# ATTINY85_Updated_Design_Extended_Board.net
KiCad netlist of a schematic drawn in EAGLE
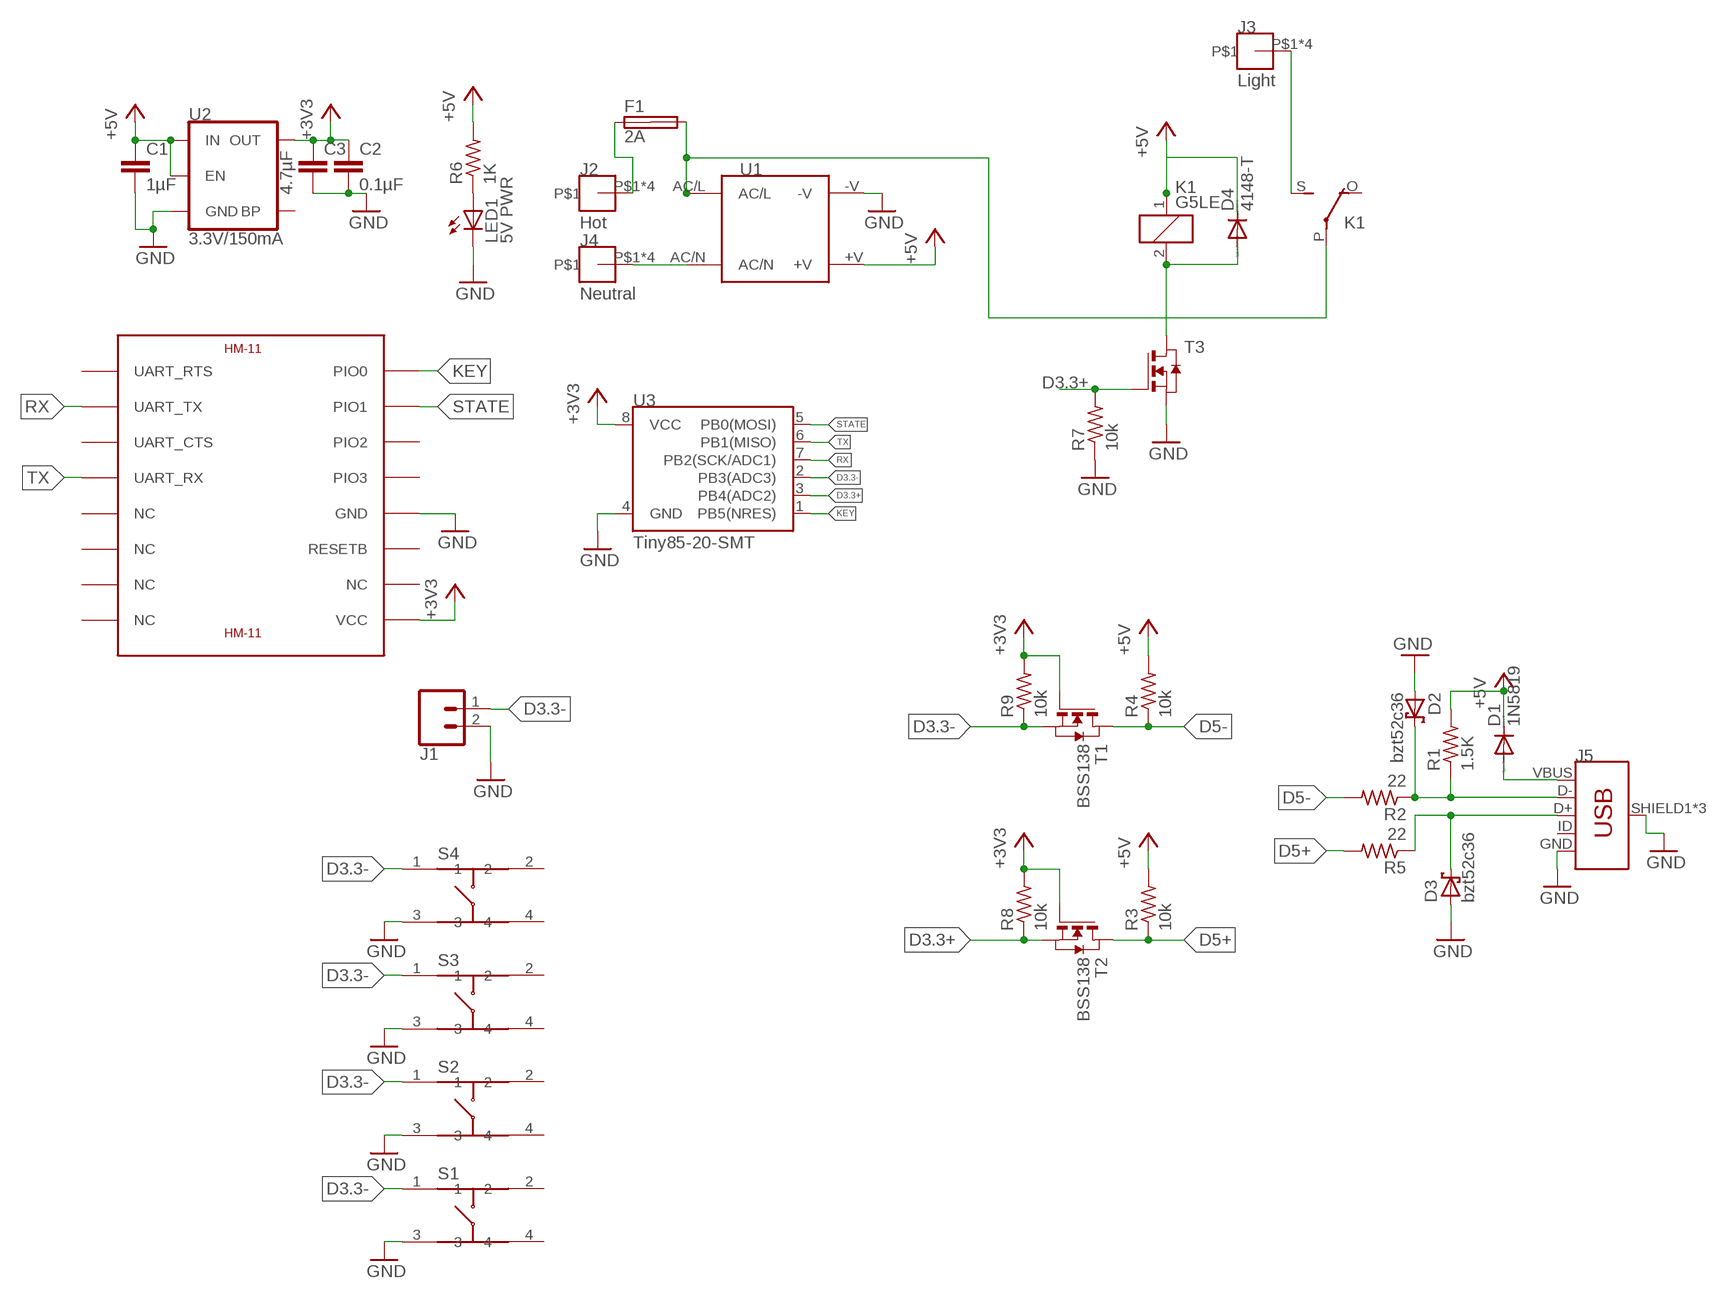
[diagram p0: schematic, sheet 1]

(export (version "E")
  (design (tool "Eeschema 10.0.6"))
  (components
    (comp (ref "C1")
      (value "1µF")
      (footprint "eagle-import:C0603K")
      (libsource (lib "eagle-import") (part "C-EUC0603K"))
    )
    (comp (ref "C2")
      (value "0.1µF")
      (footprint "eagle-import:C0603K")
      (libsource (lib "eagle-import") (part "C-EUC0603K"))
    )
    (comp (ref "C3")
      (value "4.7µF")
      (footprint "eagle-import:C0603K")
      (libsource (lib "eagle-import") (part "C-EUC0603K"))
    )
    (comp (ref "D1")
      (value "1N5819")
      (footprint "eagle-import:SOD323-R")
      (libsource (lib "eagle-import") (part "DIODE-SOD323-R"))
    )
    (comp (ref "D2")
      (value "bzt52c36")
      (footprint "eagle-import:SOD323_ST")
      (libsource (lib "eagle-import") (part "BAT60J"))
    )
    (comp (ref "D3")
      (value "bzt52c36")
      (footprint "eagle-import:SOD323_ST")
      (libsource (lib "eagle-import") (part "BAT60J"))
    )
    (comp (ref "D4")
      (value "4148-T")
      (footprint "eagle-import:SOD80C")
      (libsource (lib "eagle-import") (part "DIODE-SOD80C"))
    )
    (comp (ref "F1")
      (value "2A")
      (footprint "eagle-import:SHK20L")
      (libsource (lib "eagle-import") (part "SHK20L"))
    )
    (comp (ref "J1")
      (value "CONN_025MM")
      (footprint "eagle-import:SCREWTERMINAL-5MM-2")
      (libsource (lib "eagle-import") (part "CONN_025MM"))
    )
    (comp (ref "J2")
      (value "Hot")
      (footprint "eagle-import:7700")
      (libsource (lib "eagle-import") (part "7700"))
    )
    (comp (ref "J3")
      (value "Light")
      (footprint "eagle-import:7700")
      (libsource (lib "eagle-import") (part "7700"))
    )
    (comp (ref "J4")
      (value "Neutral")
      (footprint "eagle-import:7700")
      (libsource (lib "eagle-import") (part "7700"))
    )
    (comp (ref "J5")
      (value "USB_MICRO-B_FEMALE-SMT")
      (footprint "eagle-import:USB-B-MICRO-SMD")
      (libsource (lib "eagle-import") (part "USB_MICRO-B_FEMALE-SMT"))
    )
    (comp (ref "K1")
      (value "G5LE")
      (footprint "eagle-import:G5LE")
      (libsource (lib "eagle-import") (part "G5LE"))
    )
    (comp (ref "LED1")
      (value "5V PWR")
      (footprint "eagle-import:CHIPLED_0603")
      (libsource (lib "eagle-import") (part "LEDCHIPLED_0603"))
    )
    (comp (ref "R1")
      (value "1.5K")
      (footprint "eagle-import:R0603")
      (libsource (lib "eagle-import") (part "R-US_R0603"))
    )
    (comp (ref "R2")
      (value "22")
      (footprint "eagle-import:R0603")
      (libsource (lib "eagle-import") (part "R-US_R0603"))
    )
    (comp (ref "R3")
      (value "10k")
      (footprint "eagle-import:R0603")
      (libsource (lib "eagle-import") (part "R-US_R0603"))
    )
    (comp (ref "R4")
      (value "10k")
      (footprint "eagle-import:R0603")
      (libsource (lib "eagle-import") (part "R-US_R0603"))
    )
    (comp (ref "R5")
      (value "22")
      (footprint "eagle-import:R0603")
      (libsource (lib "eagle-import") (part "R-US_R0603"))
    )
    (comp (ref "R6")
      (value "1K")
      (footprint "eagle-import:R0603")
      (libsource (lib "eagle-import") (part "R-US_R0603"))
    )
    (comp (ref "R7")
      (value "10k")
      (footprint "eagle-import:R0603")
      (libsource (lib "eagle-import") (part "R-US_R0603"))
    )
    (comp (ref "R8")
      (value "10k")
      (footprint "eagle-import:R0603")
      (libsource (lib "eagle-import") (part "R-US_R0603"))
    )
    (comp (ref "R9")
      (value "10k")
      (footprint "eagle-import:R0603")
      (libsource (lib "eagle-import") (part "R-US_R0603"))
    )
    (comp (ref "S1")
      (value "PTS645S_SMTR92")
      (footprint "eagle-import:SMT")
      (libsource (lib "eagle-import") (part "PTS645S_SMTR92"))
    )
    (comp (ref "S2")
      (value "PTS645S_SMTR92")
      (footprint "eagle-import:SMT")
      (libsource (lib "eagle-import") (part "PTS645S_SMTR92"))
    )
    (comp (ref "S3")
      (value "PTS645S_SMTR92")
      (footprint "eagle-import:SMT")
      (libsource (lib "eagle-import") (part "PTS645S_SMTR92"))
    )
    (comp (ref "S4")
      (value "PTS645S_SMTR92")
      (footprint "eagle-import:SMT")
      (libsource (lib "eagle-import") (part "PTS645S_SMTR92"))
    )
    (comp (ref "T1")
      (value "BSS138")
      (footprint "eagle-import:SOT-23")
      (libsource (lib "eagle-import") (part "NMOSSOT23"))
    )
    (comp (ref "T2")
      (value "BSS138")
      (footprint "eagle-import:SOT-23")
      (libsource (lib "eagle-import") (part "NMOSSOT23"))
    )
    (comp (ref "T3")
      (value "NMOSSOT23")
      (footprint "eagle-import:SOT-23")
      (libsource (lib "eagle-import") (part "NMOSSOT23"))
    )
    (comp (ref "U$1")
      (value "HM-11")
      (footprint "eagle-import:HM-11")
      (libsource (lib "eagle-import") (part "HM-11"))
    )
    (comp (ref "U1")
      (value "IRM-05-5")
      (footprint "eagle-import:IRM-05")
      (libsource (lib "eagle-import") (part "IRM-05-5"))
    )
    (comp (ref "U2")
      (value "3.3V/150mA")
      (footprint "eagle-import:SOT23-5")
      (libsource (lib "eagle-import") (part "V_REG_MIC52053.3V"))
    )
    (comp (ref "U3")
      (value "Tiny85-20-SMT")
      (footprint "eagle-import:SO08-EIAJ_MCU")
      (libsource (lib "eagle-import") (part "ATTINY45TINY85-20-SMT"))
    )
  )
  (nets
    (net (code "1") (name "+3V3") (class "Default")
      (node (ref "C2") (pin "1") (pinfunction "1_1") (pintype "passive"))
      (node (ref "C3") (pin "1") (pinfunction "1_1") (pintype "passive"))
      (node (ref "R8") (pin "2") (pinfunction "2_2") (pintype "passive"))
      (node (ref "R9") (pin "2") (pinfunction "2_2") (pintype "passive"))
      (node (ref "T1") (pin "3") (pinfunction "G_3") (pintype "passive"))
      (node (ref "T2") (pin "3") (pinfunction "G_3") (pintype "passive"))
      (node (ref "U$1") (pin "VCC") (pinfunction "VCC_VCC") (pintype "bidirectional"))
      (node (ref "U2") (pin "5") (pinfunction "OUT_5") (pintype "passive"))
      (node (ref "U3") (pin "8") (pinfunction "VCC_8") (pintype "bidirectional"))
    )
    (net (code "2") (name "+5V") (class "Default")
      (node (ref "C1") (pin "1") (pinfunction "1_1") (pintype "passive"))
      (node (ref "D1") (pin "C") (pinfunction "C_C") (pintype "passive"))
      (node (ref "D4") (pin "C") (pinfunction "C_C") (pintype "passive"))
      (node (ref "K1") (pin "1") (pinfunction "1_1") (pintype "passive"))
      (node (ref "R1") (pin "2") (pinfunction "2_2") (pintype "passive"))
      (node (ref "R3") (pin "2") (pinfunction "2_2") (pintype "passive"))
      (node (ref "R4") (pin "2") (pinfunction "2_2") (pintype "passive"))
      (node (ref "R6") (pin "2") (pinfunction "2_2") (pintype "passive"))
      (node (ref "U1") (pin "+V") (pinfunction "+V_+V") (pintype "passive"))
      (node (ref "U2") (pin "1") (pinfunction "IN_1") (pintype "input"))
      (node (ref "U2") (pin "3") (pinfunction "EN_3") (pintype "input"))
    )
    (net (code "3") (name "D3.3+") (class "Default")
      (node (ref "R7") (pin "2") (pinfunction "2_2") (pintype "passive"))
      (node (ref "R8") (pin "1") (pinfunction "1_1") (pintype "passive"))
      (node (ref "T2") (pin "2") (pinfunction "S_2") (pintype "passive"))
      (node (ref "T3") (pin "3") (pinfunction "G_3") (pintype "passive"))
      (node (ref "U3") (pin "3") (pinfunction "PB4(ADC2)_3") (pintype "bidirectional"))
    )
    (net (code "4") (name "D3.3-") (class "Default")
      (node (ref "J1") (pin "1") (pinfunction "1_1") (pintype "passive"))
      (node (ref "R9") (pin "1") (pinfunction "1_1") (pintype "passive"))
      (node (ref "S1") (pin "1") (pinfunction "1_1") (pintype "bidirectional"))
      (node (ref "S2") (pin "1") (pinfunction "1_1") (pintype "bidirectional"))
      (node (ref "S3") (pin "1") (pinfunction "1_1") (pintype "bidirectional"))
      (node (ref "S4") (pin "1") (pinfunction "1_1") (pintype "bidirectional"))
      (node (ref "T1") (pin "2") (pinfunction "S_2") (pintype "passive"))
      (node (ref "U3") (pin "2") (pinfunction "PB3(ADC3)_2") (pintype "bidirectional"))
    )
    (net (code "5") (name "D5+") (class "Default")
      (node (ref "R3") (pin "1") (pinfunction "1_1") (pintype "passive"))
      (node (ref "R5") (pin "2") (pinfunction "2_2") (pintype "passive"))
      (node (ref "T2") (pin "1") (pinfunction "D_1") (pintype "passive"))
    )
    (net (code "6") (name "D5-") (class "Default")
      (node (ref "R2") (pin "2") (pinfunction "2_2") (pintype "passive"))
      (node (ref "R4") (pin "1") (pinfunction "1_1") (pintype "passive"))
      (node (ref "T1") (pin "1") (pinfunction "D_1") (pintype "passive"))
    )
    (net (code "7") (name "GND") (class "Default")
      (node (ref "C1") (pin "2") (pinfunction "2_2") (pintype "passive"))
      (node (ref "C2") (pin "2") (pinfunction "2_2") (pintype "passive"))
      (node (ref "C3") (pin "2") (pinfunction "2_2") (pintype "passive"))
      (node (ref "D2") (pin "A") (pinfunction "A_A") (pintype "passive"))
      (node (ref "D3") (pin "A") (pinfunction "A_A") (pintype "passive"))
      (node (ref "J1") (pin "2") (pinfunction "2_2") (pintype "passive"))
      (node (ref "J5") (pin "GND") (pinfunction "GND_GND") (pintype "power_in"))
      (node (ref "J5") (pin "SHIELD1") (pinfunction "SHIELD_SHIELD1") (pintype "bidirectional"))
      (node (ref "J5") (pin "SHIELD2") (pinfunction "SHIELD_SHIELD2") (pintype "bidirectional"))
      (node (ref "J5") (pin "SHIELD3") (pinfunction "SHIELD_SHIELD3") (pintype "bidirectional"))
      (node (ref "LED1") (pin "C") (pinfunction "C_C") (pintype "passive"))
      (node (ref "R7") (pin "1") (pinfunction "1_1") (pintype "passive"))
      (node (ref "S1") (pin "3") (pinfunction "3_3") (pintype "bidirectional"))
      (node (ref "S2") (pin "3") (pinfunction "3_3") (pintype "bidirectional"))
      (node (ref "S3") (pin "3") (pinfunction "3_3") (pintype "bidirectional"))
      (node (ref "S4") (pin "3") (pinfunction "3_3") (pintype "bidirectional"))
      (node (ref "T3") (pin "2") (pinfunction "S_2") (pintype "passive"))
      (node (ref "U$1") (pin "GND") (pinfunction "GND_GND") (pintype "bidirectional"))
      (node (ref "U1") (pin "-V") (pinfunction "-V_-V") (pintype "power_in"))
      (node (ref "U2") (pin "2") (pinfunction "GND_2") (pintype "input"))
      (node (ref "U3") (pin "4") (pinfunction "GND_4") (pintype "bidirectional"))
    )
    (net (code "8") (name "KEY") (class "Default")
      (node (ref "U$1") (pin "PIO0") (pinfunction "PIO0_PIO0") (pintype "bidirectional"))
      (node (ref "U3") (pin "1") (pinfunction "PB5(NRES)_1") (pintype "bidirectional"))
    )
    (net (code "9") (name "Net-(D1-PadA)") (class "Default")
      (node (ref "D1") (pin "A") (pinfunction "A_A") (pintype "passive"))
      (node (ref "J5") (pin "VBUS") (pinfunction "VBUS_VBUS") (pintype "power_in"))
    )
    (net (code "10") (name "Net-(D2-PadC)") (class "Default")
      (node (ref "D2") (pin "C") (pinfunction "C_C") (pintype "passive"))
      (node (ref "J5") (pin "D-") (pinfunction "D-_D-") (pintype "bidirectional"))
      (node (ref "R1") (pin "1") (pinfunction "1_1") (pintype "passive"))
      (node (ref "R2") (pin "1") (pinfunction "1_1") (pintype "passive"))
    )
    (net (code "11") (name "Net-(D3-PadC)") (class "Default")
      (node (ref "D3") (pin "C") (pinfunction "C_C") (pintype "passive"))
      (node (ref "J5") (pin "D+") (pinfunction "D+_D+") (pintype "bidirectional"))
      (node (ref "R5") (pin "1") (pinfunction "1_1") (pintype "passive"))
    )
    (net (code "12") (name "Net-(F1-Pad1A)") (class "Default")
      (node (ref "F1") (pin "1A") (pinfunction "1A_1A") (pintype "passive"))
      (node (ref "J2") (pin "P$1") (pinfunction "P$1_P$1") (pintype "bidirectional"))
      (node (ref "J2") (pin "P$2") (pinfunction "P$1_P$2") (pintype "bidirectional"))
      (node (ref "J2") (pin "P$3") (pinfunction "P$1_P$3") (pintype "bidirectional"))
      (node (ref "J2") (pin "P$4") (pinfunction "P$1_P$4") (pintype "bidirectional"))
    )
    (net (code "13") (name "Net-(F1-Pad2A)") (class "Default")
      (node (ref "F1") (pin "2A") (pinfunction "2A_2A") (pintype "passive"))
      (node (ref "K1") (pin "P") (pinfunction "P_P") (pintype "passive"))
      (node (ref "U1") (pin "AC/L") (pinfunction "AC/L_AC/L") (pintype "power_in"))
    )
    (net (code "14") (name "Net-(J3-P$1-PadP$2)") (class "Default")
      (node (ref "J3") (pin "P$1") (pinfunction "P$1_P$1") (pintype "bidirectional"))
      (node (ref "J3") (pin "P$2") (pinfunction "P$1_P$2") (pintype "bidirectional"))
      (node (ref "J3") (pin "P$3") (pinfunction "P$1_P$3") (pintype "bidirectional"))
      (node (ref "J3") (pin "P$4") (pinfunction "P$1_P$4") (pintype "bidirectional"))
      (node (ref "K1") (pin "S") (pinfunction "S_S") (pintype "passive"))
    )
    (net (code "15") (name "Net-(J4-P$1-PadP$2)") (class "Default")
      (node (ref "J4") (pin "P$1") (pinfunction "P$1_P$1") (pintype "bidirectional"))
      (node (ref "J4") (pin "P$2") (pinfunction "P$1_P$2") (pintype "bidirectional"))
      (node (ref "J4") (pin "P$3") (pinfunction "P$1_P$3") (pintype "bidirectional"))
      (node (ref "J4") (pin "P$4") (pinfunction "P$1_P$4") (pintype "bidirectional"))
      (node (ref "U1") (pin "AC/N") (pinfunction "AC/N_AC/N") (pintype "power_in"))
    )
    (net (code "16") (name "Net-(LED1-PadA)") (class "Default")
      (node (ref "LED1") (pin "A") (pinfunction "A_A") (pintype "passive"))
      (node (ref "R6") (pin "1") (pinfunction "1_1") (pintype "passive"))
    )
    (net (code "17") (name "Net-(T3-D)") (class "Default")
      (node (ref "D4") (pin "A") (pinfunction "A_A") (pintype "passive"))
      (node (ref "K1") (pin "2") (pinfunction "2_2") (pintype "passive"))
      (node (ref "T3") (pin "1") (pinfunction "D_1") (pintype "passive"))
    )
    (net (code "18") (name "RX") (class "Default")
      (node (ref "U$1") (pin "UART_TX") (pinfunction "UART_TX_UART_TX") (pintype "bidirectional"))
      (node (ref "U3") (pin "7") (pinfunction "PB2(SCK/ADC1)_7") (pintype "bidirectional"))
    )
    (net (code "19") (name "STATE") (class "Default")
      (node (ref "U$1") (pin "PIO1") (pinfunction "PIO1_PIO1") (pintype "bidirectional"))
      (node (ref "U3") (pin "5") (pinfunction "PB0(MOSI)_5") (pintype "bidirectional"))
    )
    (net (code "20") (name "TX") (class "Default")
      (node (ref "U$1") (pin "UART_RX") (pinfunction "UART_RX_UART_RX") (pintype "bidirectional"))
      (node (ref "U3") (pin "6") (pinfunction "PB1(MISO)_6") (pintype "bidirectional"))
    )
    (net (code "21") (name "unconnected-(F1-Pad1B)") (class "Default")
      (node (ref "F1") (pin "1B") (pinfunction "1B_1B") (pintype "passive"))
    )
    (net (code "22") (name "unconnected-(F1-Pad2B)") (class "Default")
      (node (ref "F1") (pin "2B") (pinfunction "2B_2B") (pintype "passive"))
    )
    (net (code "23") (name "unconnected-(J5-PadID)") (class "Default")
      (node (ref "J5") (pin "ID") (pinfunction "ID_ID") (pintype "bidirectional"))
    )
    (net (code "24") (name "unconnected-(K1-PadO)") (class "Default")
      (node (ref "K1") (pin "O") (pinfunction "O_O") (pintype "passive"))
    )
    (net (code "25") (name "unconnected-(S1-Pad2)") (class "Default")
      (node (ref "S1") (pin "2") (pinfunction "2_2") (pintype "bidirectional"))
    )
    (net (code "26") (name "unconnected-(S1-Pad4)") (class "Default")
      (node (ref "S1") (pin "4") (pinfunction "4_4") (pintype "bidirectional"))
    )
    (net (code "27") (name "unconnected-(S2-Pad2)") (class "Default")
      (node (ref "S2") (pin "2") (pinfunction "2_2") (pintype "bidirectional"))
    )
    (net (code "28") (name "unconnected-(S2-Pad4)") (class "Default")
      (node (ref "S2") (pin "4") (pinfunction "4_4") (pintype "bidirectional"))
    )
    (net (code "29") (name "unconnected-(S3-Pad2)") (class "Default")
      (node (ref "S3") (pin "2") (pinfunction "2_2") (pintype "bidirectional"))
    )
    (net (code "30") (name "unconnected-(S3-Pad4)") (class "Default")
      (node (ref "S3") (pin "4") (pinfunction "4_4") (pintype "bidirectional"))
    )
    (net (code "31") (name "unconnected-(S4-Pad2)") (class "Default")
      (node (ref "S4") (pin "2") (pinfunction "2_2") (pintype "bidirectional"))
    )
    (net (code "32") (name "unconnected-(S4-Pad4)") (class "Default")
      (node (ref "S4") (pin "4") (pinfunction "4_4") (pintype "bidirectional"))
    )
    (net (code "33") (name "unconnected-(U$1-NC-PadNC@5)") (class "Default")
      (node (ref "U$1") (pin "NC@5") (pinfunction "NC_NC@5") (pintype "bidirectional"))
    )
    (net (code "34") (name "unconnected-(U$1-NC-PadNC@6)") (class "Default")
      (node (ref "U$1") (pin "NC@6") (pinfunction "NC_NC@6") (pintype "bidirectional"))
    )
    (net (code "35") (name "unconnected-(U$1-NC-PadNC@7)") (class "Default")
      (node (ref "U$1") (pin "NC@7") (pinfunction "NC_NC@7") (pintype "bidirectional"))
    )
    (net (code "36") (name "unconnected-(U$1-NC-PadNC@8)") (class "Default")
      (node (ref "U$1") (pin "NC@8") (pinfunction "NC_NC@8") (pintype "bidirectional"))
    )
    (net (code "37") (name "unconnected-(U$1-NC-PadNC@10)") (class "Default")
      (node (ref "U$1") (pin "NC@10") (pinfunction "NC_NC@10") (pintype "bidirectional"))
    )
    (net (code "38") (name "unconnected-(U$1-PadPIO2)") (class "Default")
      (node (ref "U$1") (pin "PIO2") (pinfunction "PIO2_PIO2") (pintype "bidirectional"))
    )
    (net (code "39") (name "unconnected-(U$1-PadPIO3)") (class "Default")
      (node (ref "U$1") (pin "PIO3") (pinfunction "PIO3_PIO3") (pintype "bidirectional"))
    )
    (net (code "40") (name "unconnected-(U$1-PadRESETB)") (class "Default")
      (node (ref "U$1") (pin "RESETB") (pinfunction "RESETB_RESETB") (pintype "bidirectional"))
    )
    (net (code "41") (name "unconnected-(U$1-PadUART_CTS)") (class "Default")
      (node (ref "U$1") (pin "UART_CTS") (pinfunction "UART_CTS_UART_CTS") (pintype "bidirectional"))
    )
    (net (code "42") (name "unconnected-(U$1-PadUART_RTS)") (class "Default")
      (node (ref "U$1") (pin "UART_RTS") (pinfunction "UART_RTS_UART_RTS") (pintype "bidirectional"))
    )
    (net (code "43") (name "unconnected-(U2-BP-Pad4)") (class "Default")
      (node (ref "U2") (pin "4") (pinfunction "BP_4") (pintype "input"))
    )
  )
)
